# temp_lm35.net
KiCad netlist of a schematic drawn in Altium Designer
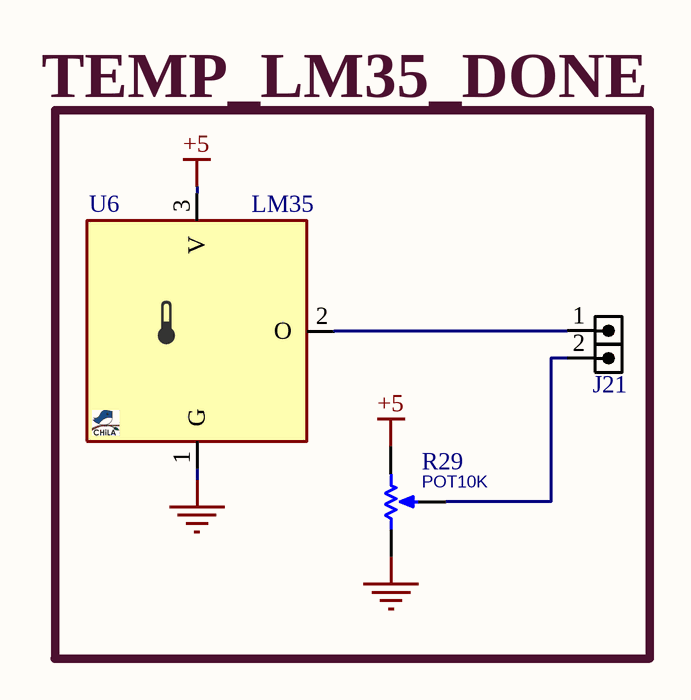
[diagram p0: temp_lm35.SchDoc]

(export (version "E")
  (design (tool "Eeschema 10.0.6"))
  (components
    (comp (ref "J21")
      (value "HDRM2")
      (footprint "HDR_M_1X2")
      (description "CONN, HEADER, Male, pitch: 2.54mm, 2POS")
      (libsource (lib "conn_header_2.54mm_st") (part "HDR_M_1X2"))
    )
    (comp (ref "R29")
      (value "POT10K")
      (footprint "POT_3296W")
      (description "RESISTOR, THD, Potentiometer")
      (libsource (lib "resistor_pot_trimmer") (part "RES_THD_POT_3296W"))
    )
    (comp (ref "U6")
      (value "LM35")
      (footprint "TO92_3")
      (description "SENSOR, TEMP, ANALOG, -55~150oC, 4~20Vcc, Out 0mV + 10mV/oC")
      (fields (field (name "MANF_P#") "LM35CZ, LM35CAZ or LM35DZ") (field (name "MANF") "TI"))
      (libsource (lib "sensor_temp&humidity") (part "TMP_LM35_TO92"))
    )
  )
  (nets
    (net (code "1") (name "+5") (class "Default")
      (node (ref "R29") (pin "3") (pinfunction "BOT_3") (pintype "passive"))
      (node (ref "U6") (pin "3") (pinfunction "V_3") (pintype "passive"))
    )
    (net (code "2") (name "GND") (class "Default")
      (node (ref "R29") (pin "1") (pinfunction "TOP_1") (pintype "passive"))
      (node (ref "U6") (pin "1") (pinfunction "G_1") (pintype "passive"))
    )
    (net (code "3") (name "Net-(R29-TAP)") (class "Default")
      (node (ref "J21") (pin "2") (pinfunction "2_2") (pintype "passive"))
      (node (ref "R29") (pin "2") (pinfunction "TAP_2") (pintype "passive"))
    )
    (net (code "4") (name "Net-(U6-O)") (class "Default")
      (node (ref "J21") (pin "1") (pinfunction "1_1") (pintype "passive"))
      (node (ref "U6") (pin "2") (pinfunction "O_2") (pintype "passive"))
    )
  )
)
